# Microcontroller.net
KiCad netlist of a schematic drawn in Altium Designer
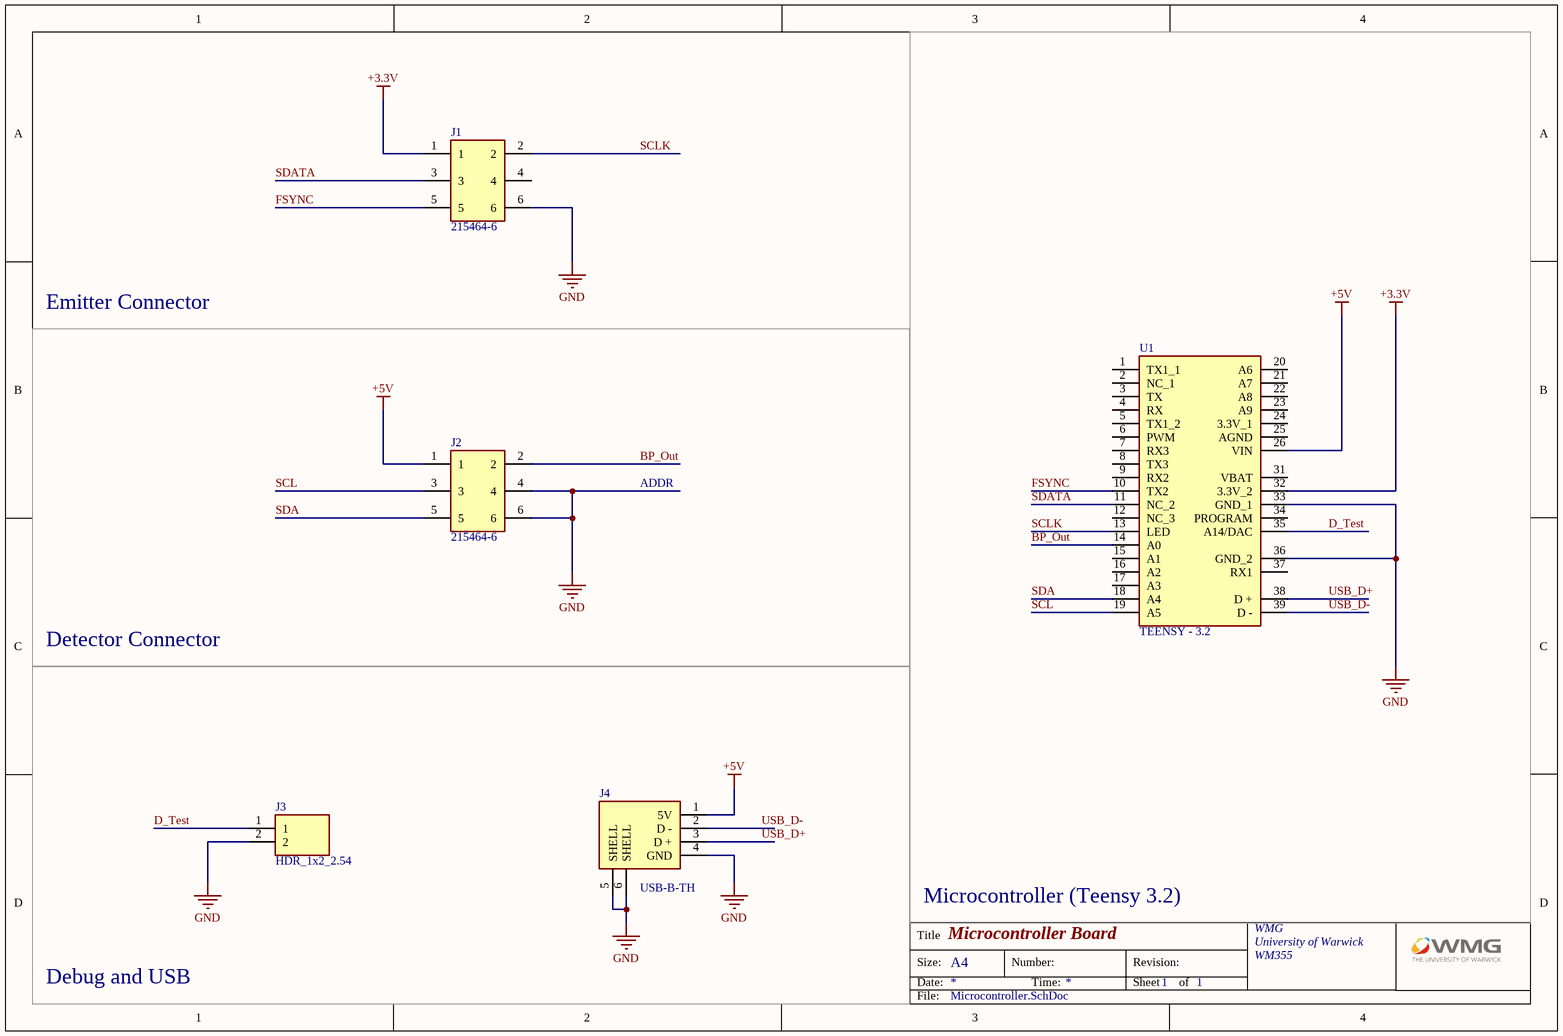
[diagram p0: Microcontroller.SchDoc]

(export (version "E")
  (design (tool "Eeschema 10.0.6"))
  (components
    (comp (ref "J1")
      (value "215464-6")
      (footprint "WM355-Altium:2154646")
      (description "Micro-Match Connector Male 6-Way")
      (fields (field (name "MOUSER PART NUMBER") "571-215464-6"))
      (libsource (lib "WM355-Altium") (part "215464-6"))
    )
    (comp (ref "J2")
      (value "215464-6")
      (footprint "WM355-Altium:2154646")
      (description "Micro-Match Connector Male 6-Way")
      (fields (field (name "MOUSER PART NUMBER") "571-215464-6"))
      (libsource (lib "WM355-Altium") (part "215464-6"))
    )
    (comp (ref "J3")
      (value "HDR_1x2_2.54")
      (footprint "WM355-Altium:HDR_1x2_2.54")
      (description "0.1\" Male Header Connector")
      (fields
        (field (name "MANUFACTURER_PART_NUMBER") "10129378-902001BLF")
        (field (name "MOUSER PART NUMBER") "649-1012937890201BLF")
      )
      (libsource (lib "WM355-Altium") (part "HDR_1x2_2.54"))
    )
    (comp (ref "J4")
      (value "USB-B-TH")
      (footprint "WM355-Altium:USB-B-TH")
      (description "USB Type B Connector - Thru-Hole")
      (fields
        (field (name "MANUFACTURER_PART_NUMBER") "292304-1")
        (field (name "MOUSER PART NUMBER") "571-292304-1")
      )
      (libsource (lib "WM355-Altium") (part "USB-B-TH"))
    )
    (comp (ref "U1")
      (value "TEENSY - 3.2")
      (footprint "WM355-Altium:TEENSY-3.2")
      (description "ARM Development Board")
      (fields (field (name "MANUFACTURER_PART_NUMBER") "TEENSY3.2"))
      (libsource (lib "WM355-Altium") (part "TEENSY-3.2"))
    )
  )
  (nets
    (net (code "1") (name "+3.3V") (class "Default")
      (node (ref "J1") (pin "1") (pinfunction "1_1") (pintype "passive"))
      (node (ref "U1") (pin "32") (pinfunction "3.3V_2_32") (pintype "passive"))
    )
    (net (code "2") (name "+5V") (class "Default")
      (node (ref "J2") (pin "1") (pinfunction "1_1") (pintype "passive"))
      (node (ref "J4") (pin "1") (pinfunction "5V_1") (pintype "passive"))
      (node (ref "U1") (pin "26") (pinfunction "VIN_26") (pintype "passive"))
    )
    (net (code "3") (name "/BP_Out") (class "Default")
      (node (ref "J2") (pin "2") (pinfunction "2_2") (pintype "passive"))
      (node (ref "U1") (pin "14") (pinfunction "A0_14") (pintype "passive"))
    )
    (net (code "4") (name "/D_Test") (class "Default")
      (node (ref "J3") (pin "1") (pinfunction "1_1") (pintype "passive"))
      (node (ref "U1") (pin "35") (pinfunction "A14/DAC_35") (pintype "passive"))
    )
    (net (code "5") (name "/FSYNC") (class "Default")
      (node (ref "J1") (pin "5") (pinfunction "5_5") (pintype "passive"))
      (node (ref "U1") (pin "10") (pinfunction "TX2_10") (pintype "passive"))
    )
    (net (code "6") (name "/SCL") (class "Default")
      (node (ref "J2") (pin "3") (pinfunction "3_3") (pintype "passive"))
      (node (ref "U1") (pin "19") (pinfunction "A5_19") (pintype "passive"))
    )
    (net (code "7") (name "/SCLK") (class "Default")
      (node (ref "J1") (pin "2") (pinfunction "2_2") (pintype "passive"))
      (node (ref "U1") (pin "13") (pinfunction "LED_13") (pintype "passive"))
    )
    (net (code "8") (name "/SDA") (class "Default")
      (node (ref "J2") (pin "5") (pinfunction "5_5") (pintype "passive"))
      (node (ref "U1") (pin "18") (pinfunction "A4_18") (pintype "passive"))
    )
    (net (code "9") (name "/SDATA") (class "Default")
      (node (ref "J1") (pin "3") (pinfunction "3_3") (pintype "passive"))
      (node (ref "U1") (pin "11") (pinfunction "NC_2_11") (pintype "passive"))
    )
    (net (code "10") (name "/USB_D+") (class "Default")
      (node (ref "J4") (pin "3") (pinfunction "D_+_3") (pintype "passive"))
      (node (ref "U1") (pin "38") (pinfunction "D_+_38") (pintype "passive"))
    )
    (net (code "11") (name "/USB_D-") (class "Default")
      (node (ref "J4") (pin "2") (pinfunction "D_-_2") (pintype "passive"))
      (node (ref "U1") (pin "39") (pinfunction "D_-_39") (pintype "passive"))
    )
    (net (code "12") (name "GND") (class "Default")
      (node (ref "J1") (pin "6") (pinfunction "6_6") (pintype "passive"))
      (node (ref "J2") (pin "4") (pinfunction "4_4") (pintype "passive"))
      (node (ref "J2") (pin "6") (pinfunction "6_6") (pintype "passive"))
      (node (ref "J3") (pin "2") (pinfunction "2_2") (pintype "passive"))
      (node (ref "J4") (pin "4") (pinfunction "GND_4") (pintype "passive"))
      (node (ref "J4") (pin "5") (pinfunction "SHELL_5") (pintype "passive"))
      (node (ref "J4") (pin "6") (pinfunction "SHELL_6") (pintype "passive"))
      (node (ref "U1") (pin "33") (pinfunction "GND_1_33") (pintype "passive"))
      (node (ref "U1") (pin "36") (pinfunction "GND_2_36") (pintype "passive"))
    )
    (net (code "13") (name "unconnected-(J1-Pad4)") (class "Default")
      (node (ref "J1") (pin "4") (pinfunction "4_4") (pintype "passive"))
    )
    (net (code "14") (name "unconnected-(U1-3.3V_1-Pad24)") (class "Default")
      (node (ref "U1") (pin "24") (pinfunction "3.3V_1_24") (pintype "passive"))
    )
    (net (code "15") (name "unconnected-(U1-A1-Pad15)") (class "Default")
      (node (ref "U1") (pin "15") (pinfunction "A1_15") (pintype "passive"))
    )
    (net (code "16") (name "unconnected-(U1-A2-Pad16)") (class "Default")
      (node (ref "U1") (pin "16") (pinfunction "A2_16") (pintype "passive"))
    )
    (net (code "17") (name "unconnected-(U1-A3-Pad17)") (class "Default")
      (node (ref "U1") (pin "17") (pinfunction "A3_17") (pintype "passive"))
    )
    (net (code "18") (name "unconnected-(U1-A6-Pad20)") (class "Default")
      (node (ref "U1") (pin "20") (pinfunction "A6_20") (pintype "passive"))
    )
    (net (code "19") (name "unconnected-(U1-A7-Pad21)") (class "Default")
      (node (ref "U1") (pin "21") (pinfunction "A7_21") (pintype "passive"))
    )
    (net (code "20") (name "unconnected-(U1-A8-Pad22)") (class "Default")
      (node (ref "U1") (pin "22") (pinfunction "A8_22") (pintype "passive"))
    )
    (net (code "21") (name "unconnected-(U1-A9-Pad23)") (class "Default")
      (node (ref "U1") (pin "23") (pinfunction "A9_23") (pintype "passive"))
    )
    (net (code "22") (name "unconnected-(U1-AGND-Pad25)") (class "Default")
      (node (ref "U1") (pin "25") (pinfunction "AGND_25") (pintype "passive"))
    )
    (net (code "23") (name "unconnected-(U1-NC_1-Pad2)") (class "Default")
      (node (ref "U1") (pin "2") (pinfunction "NC_1_2") (pintype "passive"))
    )
    (net (code "24") (name "unconnected-(U1-NC_3-Pad12)") (class "Default")
      (node (ref "U1") (pin "12") (pinfunction "NC_3_12") (pintype "passive"))
    )
    (net (code "25") (name "unconnected-(U1-PROGRAM-Pad34)") (class "Default")
      (node (ref "U1") (pin "34") (pinfunction "PROGRAM_34") (pintype "passive"))
    )
    (net (code "26") (name "unconnected-(U1-PWM-Pad6)") (class "Default")
      (node (ref "U1") (pin "6") (pinfunction "PWM_6") (pintype "passive"))
    )
    (net (code "27") (name "unconnected-(U1-RX-Pad4)") (class "Default")
      (node (ref "U1") (pin "4") (pinfunction "RX_4") (pintype "passive"))
    )
    (net (code "28") (name "unconnected-(U1-RX1-Pad37)") (class "Default")
      (node (ref "U1") (pin "37") (pinfunction "RX1_37") (pintype "passive"))
    )
    (net (code "29") (name "unconnected-(U1-RX2-Pad9)") (class "Default")
      (node (ref "U1") (pin "9") (pinfunction "RX2_9") (pintype "passive"))
    )
    (net (code "30") (name "unconnected-(U1-RX3-Pad7)") (class "Default")
      (node (ref "U1") (pin "7") (pinfunction "RX3_7") (pintype "passive"))
    )
    (net (code "31") (name "unconnected-(U1-TX-Pad3)") (class "Default")
      (node (ref "U1") (pin "3") (pinfunction "TX_3") (pintype "passive"))
    )
    (net (code "32") (name "unconnected-(U1-TX1_1-Pad1)") (class "Default")
      (node (ref "U1") (pin "1") (pinfunction "TX1_1_1") (pintype "passive"))
    )
    (net (code "33") (name "unconnected-(U1-TX1_2-Pad5)") (class "Default")
      (node (ref "U1") (pin "5") (pinfunction "TX1_2_5") (pintype "passive"))
    )
    (net (code "34") (name "unconnected-(U1-TX3-Pad8)") (class "Default")
      (node (ref "U1") (pin "8") (pinfunction "TX3_8") (pintype "passive"))
    )
    (net (code "35") (name "unconnected-(U1-VBAT-Pad31)") (class "Default")
      (node (ref "U1") (pin "31") (pinfunction "VBAT_31") (pintype "passive"))
    )
  )
)
